# Breakout1v1.net
KiCad netlist of a schematic drawn in EAGLE
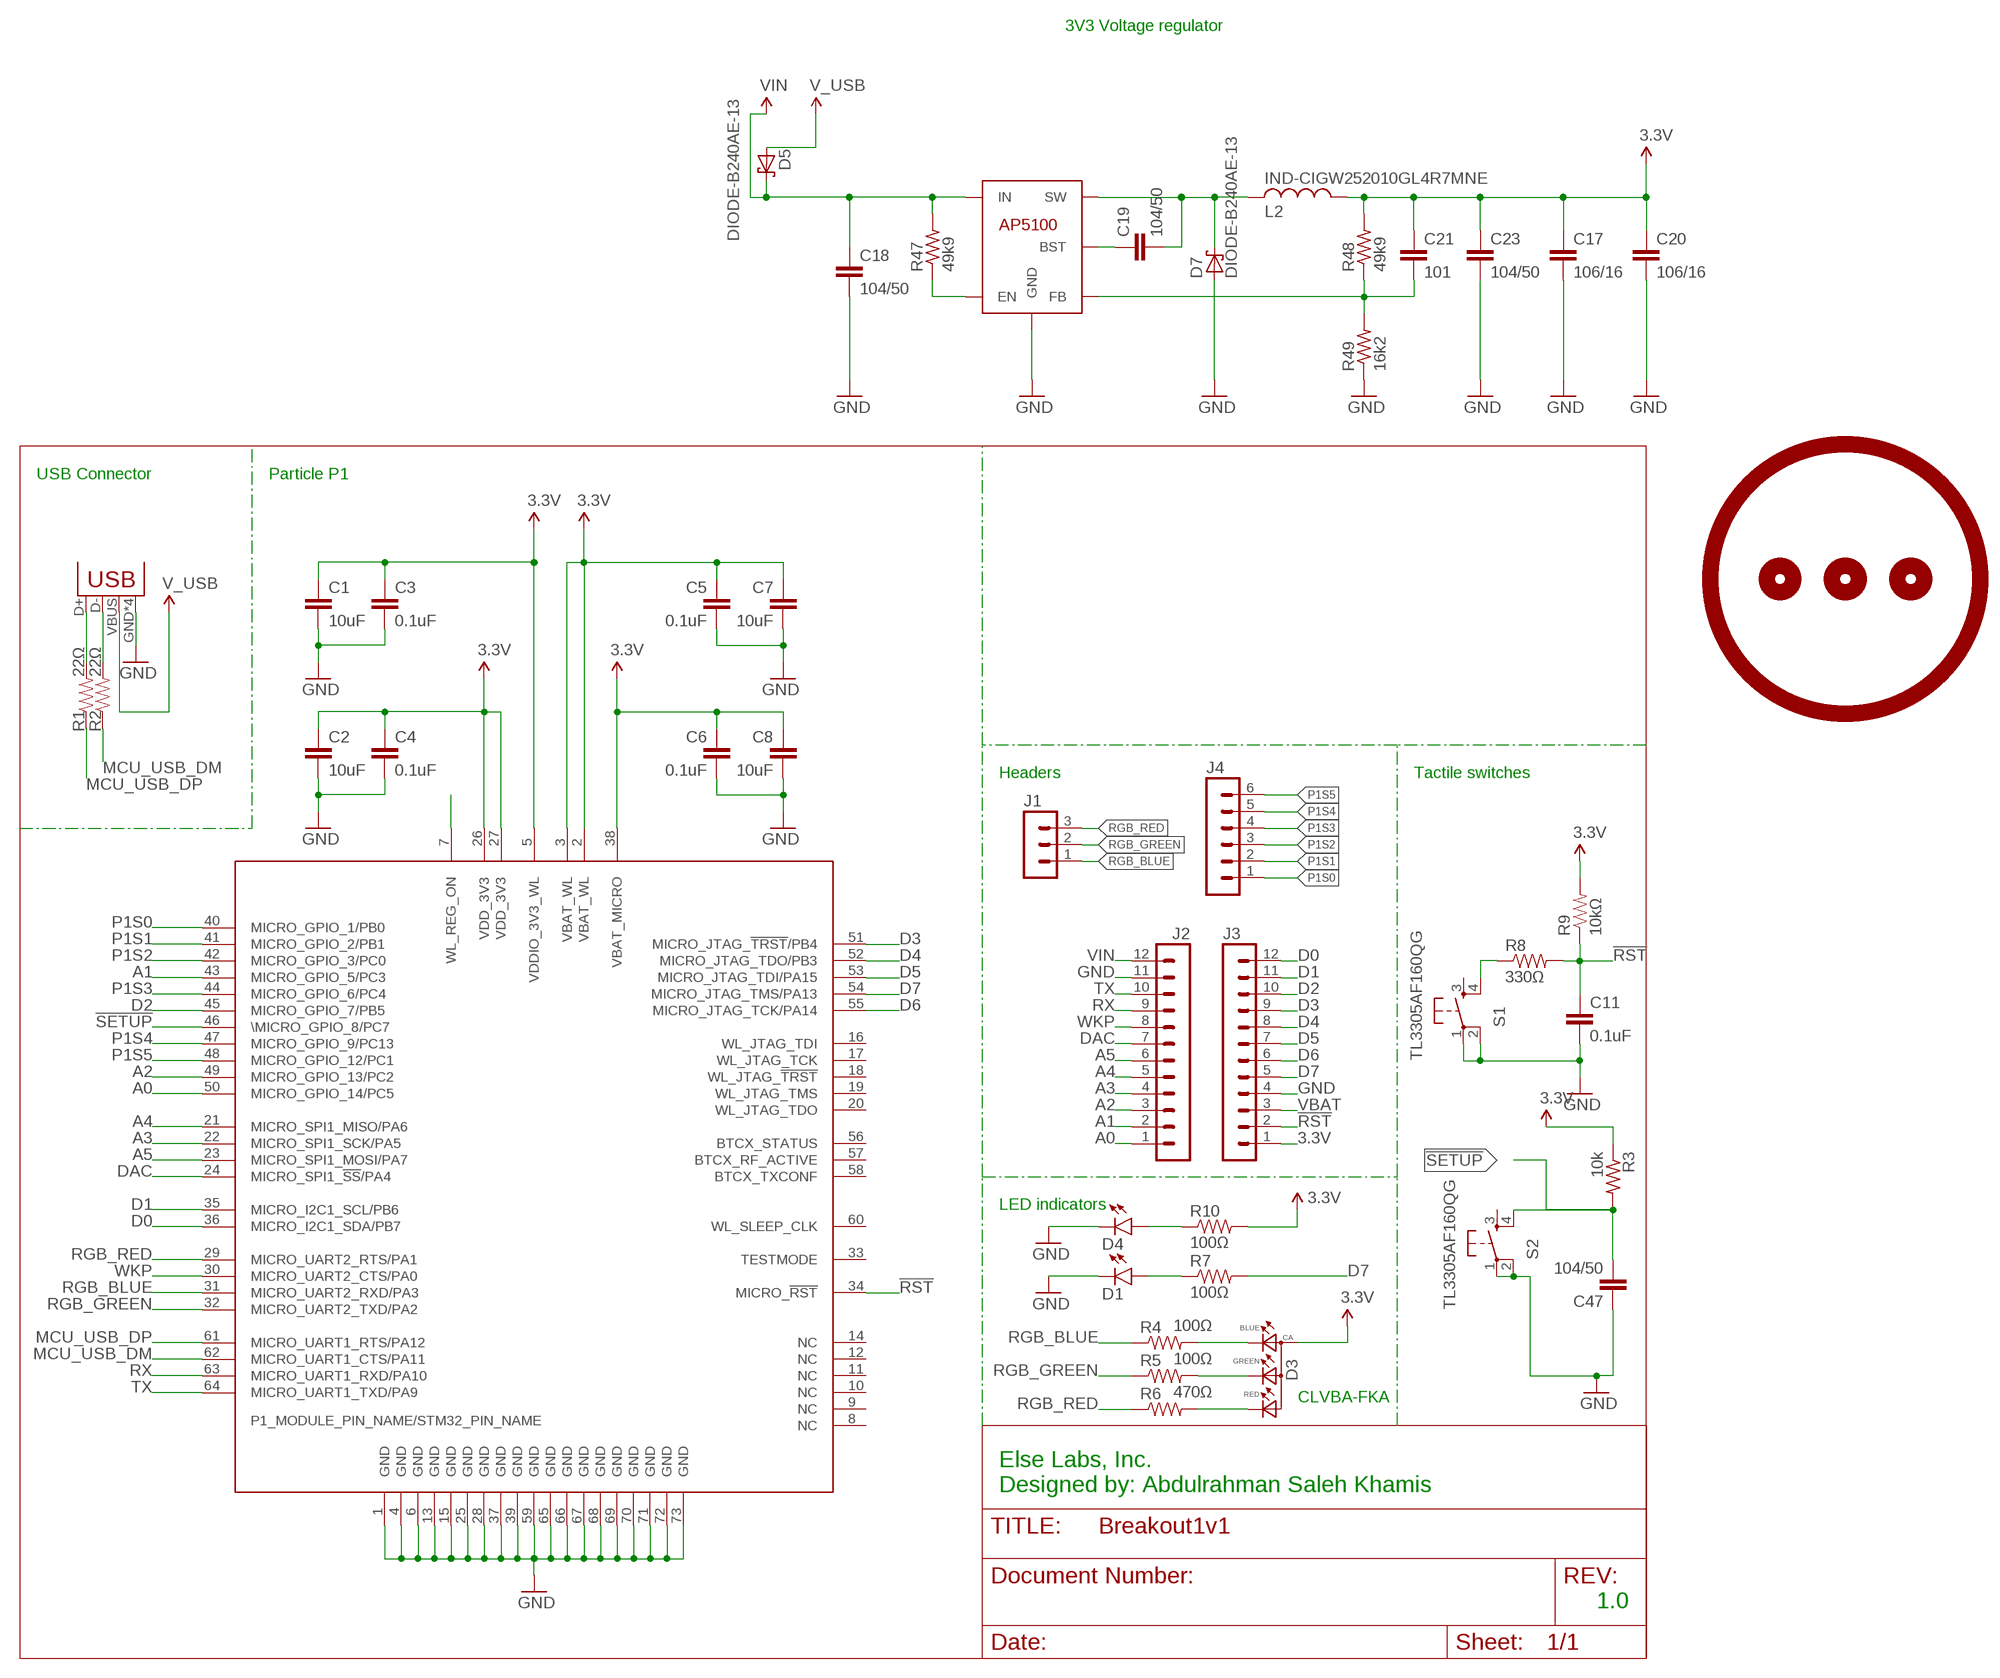
[diagram p0: schematic, sheet 1]

(export (version "E")
  (design (tool "Eeschema 10.0.6"))
  (components
    (comp (ref "C1")
      (value "10uF")
      (footprint "eagle-import:0805")
      (libsource (lib "eagle-import") (part "CAP0805"))
    )
    (comp (ref "C2")
      (value "10uF")
      (footprint "eagle-import:0805")
      (libsource (lib "eagle-import") (part "CAP0805"))
    )
    (comp (ref "C3")
      (value "0.1uF")
      (footprint "eagle-import:0805")
      (libsource (lib "eagle-import") (part "CAP0805"))
    )
    (comp (ref "C4")
      (value "0.1uF")
      (footprint "eagle-import:0805")
      (libsource (lib "eagle-import") (part "CAP0805"))
    )
    (comp (ref "C5")
      (value "0.1uF")
      (footprint "eagle-import:0805")
      (libsource (lib "eagle-import") (part "CAP0805"))
    )
    (comp (ref "C6")
      (value "0.1uF")
      (footprint "eagle-import:0805")
      (libsource (lib "eagle-import") (part "CAP0805"))
    )
    (comp (ref "C7")
      (value "10uF")
      (footprint "eagle-import:0805")
      (libsource (lib "eagle-import") (part "CAP0805"))
    )
    (comp (ref "C8")
      (value "10uF")
      (footprint "eagle-import:0805")
      (libsource (lib "eagle-import") (part "CAP0805"))
    )
    (comp (ref "C11")
      (value "0.1uF")
      (footprint "eagle-import:0805")
      (libsource (lib "eagle-import") (part "CAP0805"))
    )
    (comp (ref "C17")
      (value "106/16")
      (footprint "eagle-import:C0805")
      (libsource (lib "eagle-import") (part "C-EUC0805"))
    )
    (comp (ref "C18")
      (value "104/50")
      (footprint "eagle-import:C0603")
      (libsource (lib "eagle-import") (part "C-EUC0603"))
    )
    (comp (ref "C19")
      (value "104/50")
      (footprint "eagle-import:C0603")
      (libsource (lib "eagle-import") (part "C-EUC0603"))
    )
    (comp (ref "C20")
      (value "106/16")
      (footprint "eagle-import:C0805")
      (libsource (lib "eagle-import") (part "C-EUC0805"))
    )
    (comp (ref "C21")
      (value "101")
      (footprint "eagle-import:C0603")
      (libsource (lib "eagle-import") (part "C-EUC0603"))
    )
    (comp (ref "C23")
      (value "104/50")
      (footprint "eagle-import:C0603")
      (libsource (lib "eagle-import") (part "C-EUC0603"))
    )
    (comp (ref "C47")
      (value "104/50")
      (footprint "eagle-import:C0603")
      (libsource (lib "eagle-import") (part "C-EUC0603"))
    )
    (comp (ref "D1")
      (value "LED0603")
      (footprint "eagle-import:LED-0603")
      (libsource (lib "eagle-import") (part "LED0603"))
    )
    (comp (ref "D3")
      (value "CLVBA-FKAPLCC")
      (footprint "eagle-import:4-PLCC")
      (libsource (lib "eagle-import") (part "CLVBA-FKAPLCC"))
    )
    (comp (ref "D4")
      (value "LED0603")
      (footprint "eagle-import:LED-0603")
      (libsource (lib "eagle-import") (part "LED0603"))
    )
    (comp (ref "D5")
      (value "DIODE-B240AE-13")
      (footprint "eagle-import:DO-214AC")
      (libsource (lib "eagle-import") (part "DIODE-B240AE-13"))
    )
    (comp (ref "D7")
      (value "DIODE-B240AE-13")
      (footprint "eagle-import:DO-214AC")
      (libsource (lib "eagle-import") (part "DIODE-B240AE-13"))
    )
    (comp (ref "IC5")
      (value "SMSP-BUCK-AP5100")
      (footprint "eagle-import:SOT23-6")
      (libsource (lib "eagle-import") (part "SMSP-BUCK-AP5100"))
    )
    (comp (ref "J1")
      (value "MA03-1")
      (footprint "eagle-import:MA03-1")
      (libsource (lib "eagle-import") (part "MA03-1"))
    )
    (comp (ref "J2")
      (value "MA12-1")
      (footprint "eagle-import:MA12-1")
      (libsource (lib "eagle-import") (part "MA12-1"))
    )
    (comp (ref "J3")
      (value "MA12-1")
      (footprint "eagle-import:MA12-1")
      (libsource (lib "eagle-import") (part "MA12-1"))
    )
    (comp (ref "J4")
      (value "MA06-1")
      (footprint "eagle-import:MA06-1")
      (libsource (lib "eagle-import") (part "MA06-1"))
    )
    (comp (ref "JP1")
      (value "USBUSB-MICROB-SLOT-HOLE")
      (footprint "eagle-import:USB-MICROB-SLOT-HOLE")
      (libsource (lib "eagle-import") (part "USBUSB-MICROB-SLOT-HOLE"))
    )
    (comp (ref "L2")
      (value "IND-CIGW252010GL4R7MNE")
      (footprint "eagle-import:L2520")
      (libsource (lib "eagle-import") (part "IND-CIGW252010GL4R7MNE"))
    )
    (comp (ref "R1")
      (value "22Ω")
      (footprint "eagle-import:0805")
      (libsource (lib "eagle-import") (part "RESISTOR0805-RES"))
    )
    (comp (ref "R2")
      (value "22Ω")
      (footprint "eagle-import:0805")
      (libsource (lib "eagle-import") (part "RESISTOR0805-RES"))
    )
    (comp (ref "R3")
      (value "10k")
      (footprint "eagle-import:R0603")
      (libsource (lib "eagle-import") (part "R-US_R0603"))
    )
    (comp (ref "R4")
      (value "100Ω")
      (footprint "eagle-import:0805")
      (libsource (lib "eagle-import") (part "RESISTOR0805-RES"))
    )
    (comp (ref "R5")
      (value "100Ω")
      (footprint "eagle-import:0805")
      (libsource (lib "eagle-import") (part "RESISTOR0805-RES"))
    )
    (comp (ref "R6")
      (value "470Ω")
      (footprint "eagle-import:0805")
      (libsource (lib "eagle-import") (part "RESISTOR0805-RES"))
    )
    (comp (ref "R7")
      (value "100Ω")
      (footprint "eagle-import:0805")
      (libsource (lib "eagle-import") (part "RESISTOR0805-RES"))
    )
    (comp (ref "R8")
      (value "330Ω")
      (footprint "eagle-import:0805")
      (libsource (lib "eagle-import") (part "RESISTOR0805-RES"))
    )
    (comp (ref "R9")
      (value "10kΩ")
      (footprint "eagle-import:0805")
      (libsource (lib "eagle-import") (part "RESISTOR0805-RES"))
    )
    (comp (ref "R10")
      (value "100Ω")
      (footprint "eagle-import:0805")
      (libsource (lib "eagle-import") (part "RESISTOR0805-RES"))
    )
    (comp (ref "R47")
      (value "49k9")
      (footprint "eagle-import:R0603")
      (libsource (lib "eagle-import") (part "R-US_R0603"))
    )
    (comp (ref "R48")
      (value "49k9")
      (footprint "eagle-import:R0603")
      (libsource (lib "eagle-import") (part "R-US_R0603"))
    )
    (comp (ref "R49")
      (value "16k2")
      (footprint "eagle-import:R0603")
      (libsource (lib "eagle-import") (part "R-US_R0603"))
    )
    (comp (ref "S1")
      (value "TL3305AF160QG")
      (footprint "eagle-import:TACTILE_SWITCH_SMD_4.5X4.5MM")
      (libsource (lib "eagle-import") (part "SWITCH-MOMENTARY-4.5MX4.5M"))
    )
    (comp (ref "S2")
      (value "TL3305AF160QG")
      (footprint "eagle-import:TACTILE_SWITCH_SMD_4.5X4.5MM")
      (libsource (lib "eagle-import") (part "SWITCH-MOMENTARY-4.5MX4.5M"))
    )
    (comp (ref "U$1")
      (value "LOGO")
      (footprint "eagle-import:LOGO")
      (libsource (lib "eagle-import") (part "LOGO"))
    )
    (comp (ref "UC1")
      (value "P1")
      (footprint "eagle-import:WM-N-BM-14")
      (libsource (lib "eagle-import") (part "P1"))
    )
  )
  (nets
    (net (code "1") (name "/A0") (class "Default")
      (node (ref "J2") (pin "1") (pinfunction "1_1") (pintype "passive"))
      (node (ref "UC1") (pin "50") (pinfunction "MICRO_GPIO_14/PC5_50") (pintype "bidirectional"))
    )
    (net (code "2") (name "/A1") (class "Default")
      (node (ref "J2") (pin "2") (pinfunction "2_2") (pintype "passive"))
      (node (ref "UC1") (pin "43") (pinfunction "MICRO_GPIO_5/PC3_43") (pintype "bidirectional"))
    )
    (net (code "3") (name "/A2") (class "Default")
      (node (ref "J2") (pin "3") (pinfunction "3_3") (pintype "passive"))
      (node (ref "UC1") (pin "49") (pinfunction "MICRO_GPIO_13/PC2_49") (pintype "bidirectional"))
    )
    (net (code "4") (name "/A3") (class "Default")
      (node (ref "J2") (pin "4") (pinfunction "4_4") (pintype "passive"))
      (node (ref "UC1") (pin "22") (pinfunction "MICRO_SPI1_SCK/PA5_22") (pintype "bidirectional"))
    )
    (net (code "5") (name "/A4") (class "Default")
      (node (ref "J2") (pin "5") (pinfunction "5_5") (pintype "passive"))
      (node (ref "UC1") (pin "21") (pinfunction "MICRO_SPI1_MISO/PA6_21") (pintype "bidirectional"))
    )
    (net (code "6") (name "/A5") (class "Default")
      (node (ref "J2") (pin "6") (pinfunction "6_6") (pintype "passive"))
      (node (ref "UC1") (pin "23") (pinfunction "MICRO_SPI1_MOSI/PA7_23") (pintype "bidirectional"))
    )
    (net (code "7") (name "/D0") (class "Default")
      (node (ref "J3") (pin "12") (pinfunction "12_12") (pintype "passive"))
      (node (ref "UC1") (pin "36") (pinfunction "MICRO_I2C1_SDA/PB7_36") (pintype "bidirectional"))
    )
    (net (code "8") (name "/D1") (class "Default")
      (node (ref "J3") (pin "11") (pinfunction "11_11") (pintype "passive"))
      (node (ref "UC1") (pin "35") (pinfunction "MICRO_I2C1_SCL/PB6_35") (pintype "bidirectional"))
    )
    (net (code "9") (name "/D2") (class "Default")
      (node (ref "J3") (pin "10") (pinfunction "10_10") (pintype "passive"))
      (node (ref "UC1") (pin "45") (pinfunction "MICRO_GPIO_7/PB5_45") (pintype "bidirectional"))
    )
    (net (code "10") (name "/D3") (class "Default")
      (node (ref "J3") (pin "9") (pinfunction "9_9") (pintype "passive"))
      (node (ref "UC1") (pin "51") (pinfunction "MICRO_JTAG_~{TRST}/PB4_51") (pintype "bidirectional"))
    )
    (net (code "11") (name "/D4") (class "Default")
      (node (ref "J3") (pin "8") (pinfunction "8_8") (pintype "passive"))
      (node (ref "UC1") (pin "52") (pinfunction "MICRO_JTAG_TDO/PB3_52") (pintype "bidirectional"))
    )
    (net (code "12") (name "/D5") (class "Default")
      (node (ref "J3") (pin "7") (pinfunction "7_7") (pintype "passive"))
      (node (ref "UC1") (pin "53") (pinfunction "MICRO_JTAG_TDI/PA15_53") (pintype "bidirectional"))
    )
    (net (code "13") (name "/D6") (class "Default")
      (node (ref "J3") (pin "6") (pinfunction "6_6") (pintype "passive"))
      (node (ref "UC1") (pin "55") (pinfunction "MICRO_JTAG_TCK/PA14_55") (pintype "bidirectional"))
    )
    (net (code "14") (name "/D7") (class "Default")
      (node (ref "J3") (pin "5") (pinfunction "5_5") (pintype "passive"))
      (node (ref "R7") (pin "2") (pinfunction "2_2") (pintype "passive"))
      (node (ref "UC1") (pin "54") (pinfunction "MICRO_JTAG_TMS/PA13_54") (pintype "bidirectional"))
    )
    (net (code "15") (name "/DAC") (class "Default")
      (node (ref "J2") (pin "7") (pinfunction "7_7") (pintype "passive"))
      (node (ref "UC1") (pin "24") (pinfunction "MICRO_SPI1_~{SS}/PA4_24") (pintype "bidirectional"))
    )
    (net (code "16") (name "/MCU_USB_DM") (class "Default")
      (node (ref "R2") (pin "1") (pinfunction "1_1") (pintype "passive"))
      (node (ref "UC1") (pin "62") (pinfunction "MICRO_UART1_CTS/PA11_62") (pintype "bidirectional"))
    )
    (net (code "17") (name "/MCU_USB_DP") (class "Default")
      (node (ref "R1") (pin "1") (pinfunction "1_1") (pintype "passive"))
      (node (ref "UC1") (pin "61") (pinfunction "MICRO_UART1_RTS/PA12_61") (pintype "bidirectional"))
    )
    (net (code "18") (name "/RX") (class "Default")
      (node (ref "J2") (pin "9") (pinfunction "9_9") (pintype "passive"))
      (node (ref "UC1") (pin "63") (pinfunction "MICRO_UART1_RXD/PA10_63") (pintype "bidirectional"))
    )
    (net (code "19") (name "/TX") (class "Default")
      (node (ref "J2") (pin "10") (pinfunction "10_10") (pintype "passive"))
      (node (ref "UC1") (pin "64") (pinfunction "MICRO_UART1_TXD/PA9_64") (pintype "bidirectional"))
    )
    (net (code "20") (name "/VBAT") (class "Default")
      (node (ref "J3") (pin "3") (pinfunction "3_3") (pintype "passive"))
    )
    (net (code "21") (name "/WKP") (class "Default")
      (node (ref "J2") (pin "8") (pinfunction "8_8") (pintype "passive"))
      (node (ref "UC1") (pin "30") (pinfunction "MICRO_UART2_CTS/PA0_30") (pintype "bidirectional"))
    )
    (net (code "22") (name "/~{RST}") (class "Default")
      (node (ref "C11") (pin "1") (pinfunction "1_1") (pintype "passive"))
      (node (ref "J3") (pin "2") (pinfunction "2_2") (pintype "passive"))
      (node (ref "R8") (pin "2") (pinfunction "2_2") (pintype "passive"))
      (node (ref "R9") (pin "1") (pinfunction "1_1") (pintype "passive"))
      (node (ref "UC1") (pin "34") (pinfunction "MICRO_~{RST}_34") (pintype "bidirectional"))
    )
    (net (code "23") (name "/~{SETUP}") (class "Default")
      (node (ref "C47") (pin "2") (pinfunction "2_2") (pintype "passive"))
      (node (ref "R3") (pin "2") (pinfunction "2_2") (pintype "passive"))
      (node (ref "S2") (pin "4") (pinfunction "4_4") (pintype "passive"))
      (node (ref "UC1") (pin "46") (pinfunction "\\MICRO_GPIO_8/PC7_46") (pintype "bidirectional"))
    )
    (net (code "24") (name "3.3V") (class "Default")
      (node (ref "C1") (pin "1") (pinfunction "1_1") (pintype "passive"))
      (node (ref "C17") (pin "1") (pinfunction "1_1") (pintype "passive"))
      (node (ref "C2") (pin "1") (pinfunction "1_1") (pintype "passive"))
      (node (ref "C20") (pin "1") (pinfunction "1_1") (pintype "passive"))
      (node (ref "C21") (pin "1") (pinfunction "1_1") (pintype "passive"))
      (node (ref "C23") (pin "1") (pinfunction "1_1") (pintype "passive"))
      (node (ref "C3") (pin "1") (pinfunction "1_1") (pintype "passive"))
      (node (ref "C4") (pin "1") (pinfunction "1_1") (pintype "passive"))
      (node (ref "C5") (pin "1") (pinfunction "1_1") (pintype "passive"))
      (node (ref "C6") (pin "1") (pinfunction "1_1") (pintype "passive"))
      (node (ref "C7") (pin "1") (pinfunction "1_1") (pintype "passive"))
      (node (ref "C8") (pin "1") (pinfunction "1_1") (pintype "passive"))
      (node (ref "D3") (pin "2") (pinfunction "ANODE_2") (pintype "passive"))
      (node (ref "J3") (pin "1") (pinfunction "1_1") (pintype "passive"))
      (node (ref "L2") (pin "P$1") (pinfunction "1_P$1") (pintype "passive"))
      (node (ref "R10") (pin "2") (pinfunction "2_2") (pintype "passive"))
      (node (ref "R3") (pin "1") (pinfunction "1_1") (pintype "passive"))
      (node (ref "R48") (pin "2") (pinfunction "2_2") (pintype "passive"))
      (node (ref "R9") (pin "2") (pinfunction "2_2") (pintype "passive"))
      (node (ref "UC1") (pin "2") (pinfunction "VBAT_WL_2") (pintype "bidirectional"))
      (node (ref "UC1") (pin "26") (pinfunction "VDD_3V3_26") (pintype "bidirectional"))
      (node (ref "UC1") (pin "27") (pinfunction "VDD_3V3_27") (pintype "bidirectional"))
      (node (ref "UC1") (pin "3") (pinfunction "VBAT_WL_3") (pintype "bidirectional"))
      (node (ref "UC1") (pin "38") (pinfunction "VBAT_MICRO_38") (pintype "bidirectional"))
      (node (ref "UC1") (pin "5") (pinfunction "VDDIO_3V3_WL_5") (pintype "bidirectional"))
    )
    (net (code "25") (name "GND") (class "Default")
      (node (ref "C1") (pin "2") (pinfunction "2_2") (pintype "passive"))
      (node (ref "C11") (pin "2") (pinfunction "2_2") (pintype "passive"))
      (node (ref "C17") (pin "2") (pinfunction "2_2") (pintype "passive"))
      (node (ref "C18") (pin "2") (pinfunction "2_2") (pintype "passive"))
      (node (ref "C2") (pin "2") (pinfunction "2_2") (pintype "passive"))
      (node (ref "C20") (pin "2") (pinfunction "2_2") (pintype "passive"))
      (node (ref "C23") (pin "2") (pinfunction "2_2") (pintype "passive"))
      (node (ref "C3") (pin "2") (pinfunction "2_2") (pintype "passive"))
      (node (ref "C4") (pin "2") (pinfunction "2_2") (pintype "passive"))
      (node (ref "C47") (pin "1") (pinfunction "1_1") (pintype "passive"))
      (node (ref "C5") (pin "2") (pinfunction "2_2") (pintype "passive"))
      (node (ref "C6") (pin "2") (pinfunction "2_2") (pintype "passive"))
      (node (ref "C7") (pin "2") (pinfunction "2_2") (pintype "passive"))
      (node (ref "C8") (pin "2") (pinfunction "2_2") (pintype "passive"))
      (node (ref "D1") (pin "C") (pinfunction "C_C") (pintype "passive"))
      (node (ref "D4") (pin "C") (pinfunction "C_C") (pintype "passive"))
      (node (ref "D7") (pin "A") (pinfunction "A_A") (pintype "passive"))
      (node (ref "IC5") (pin "2") (pinfunction "GND_2") (pintype "bidirectional"))
      (node (ref "J2") (pin "11") (pinfunction "11_11") (pintype "passive"))
      (node (ref "J3") (pin "4") (pinfunction "4_4") (pintype "passive"))
      (node (ref "JP1") (pin "GND") (pinfunction "GND_GND") (pintype "bidirectional"))
      (node (ref "JP1") (pin "P$1") (pinfunction "GND_P$1") (pintype "bidirectional"))
      (node (ref "JP1") (pin "P$2") (pinfunction "GND_P$2") (pintype "bidirectional"))
      (node (ref "JP1") (pin "P$3") (pinfunction "GND_P$3") (pintype "bidirectional"))
      (node (ref "R49") (pin "1") (pinfunction "1_1") (pintype "passive"))
      (node (ref "S1") (pin "1") (pinfunction "1_1") (pintype "passive"))
      (node (ref "S1") (pin "2") (pinfunction "2_2") (pintype "passive"))
      (node (ref "S2") (pin "1") (pinfunction "1_1") (pintype "passive"))
      (node (ref "S2") (pin "2") (pinfunction "2_2") (pintype "passive"))
      (node (ref "UC1") (pin "1") (pinfunction "GND_1") (pintype "bidirectional"))
      (node (ref "UC1") (pin "13") (pinfunction "GND_13") (pintype "bidirectional"))
      (node (ref "UC1") (pin "15") (pinfunction "GND_15") (pintype "bidirectional"))
      (node (ref "UC1") (pin "25") (pinfunction "GND_25") (pintype "bidirectional"))
      (node (ref "UC1") (pin "28") (pinfunction "GND_28") (pintype "bidirectional"))
      (node (ref "UC1") (pin "37") (pinfunction "GND_37") (pintype "bidirectional"))
      (node (ref "UC1") (pin "39") (pinfunction "GND_39") (pintype "bidirectional"))
      (node (ref "UC1") (pin "4") (pinfunction "GND_4") (pintype "bidirectional"))
      (node (ref "UC1") (pin "59") (pinfunction "GND_59") (pintype "bidirectional"))
      (node (ref "UC1") (pin "6") (pinfunction "GND_6") (pintype "bidirectional"))
      (node (ref "UC1") (pin "65") (pinfunction "GND_65") (pintype "bidirectional"))
      (node (ref "UC1") (pin "66") (pinfunction "GND_66") (pintype "bidirectional"))
      (node (ref "UC1") (pin "67") (pinfunction "GND_67") (pintype "bidirectional"))
      (node (ref "UC1") (pin "68") (pinfunction "GND_68") (pintype "bidirectional"))
      (node (ref "UC1") (pin "69") (pinfunction "GND_69") (pintype "bidirectional"))
      (node (ref "UC1") (pin "70") (pinfunction "GND_70") (pintype "bidirectional"))
      (node (ref "UC1") (pin "71") (pinfunction "GND_71") (pintype "bidirectional"))
      (node (ref "UC1") (pin "72") (pinfunction "GND_72") (pintype "bidirectional"))
      (node (ref "UC1") (pin "73") (pinfunction "GND_73") (pintype "bidirectional"))
    )
    (net (code "26") (name "Net-(D1-PadA)") (class "Default")
      (node (ref "D1") (pin "A") (pinfunction "A_A") (pintype "passive"))
      (node (ref "R7") (pin "1") (pinfunction "1_1") (pintype "passive"))
    )
    (net (code "27") (name "Net-(D3-BLUE)") (class "Default")
      (node (ref "D3") (pin "3") (pinfunction "BLUE_3") (pintype "passive"))
      (node (ref "R4") (pin "2") (pinfunction "2_2") (pintype "passive"))
    )
    (net (code "28") (name "Net-(D3-GREEN)") (class "Default")
      (node (ref "D3") (pin "4") (pinfunction "GREEN_4") (pintype "passive"))
      (node (ref "R5") (pin "2") (pinfunction "2_2") (pintype "passive"))
    )
    (net (code "29") (name "Net-(D3-RED)") (class "Default")
      (node (ref "D3") (pin "1") (pinfunction "RED_1") (pintype "passive"))
      (node (ref "R6") (pin "2") (pinfunction "2_2") (pintype "passive"))
    )
    (net (code "30") (name "Net-(D4-PadA)") (class "Default")
      (node (ref "D4") (pin "A") (pinfunction "A_A") (pintype "passive"))
      (node (ref "R10") (pin "1") (pinfunction "1_1") (pintype "passive"))
    )
    (net (code "31") (name "Net-(IC5-BST)") (class "Default")
      (node (ref "C19") (pin "1") (pinfunction "1_1") (pintype "passive"))
      (node (ref "IC5") (pin "1") (pinfunction "BST_1") (pintype "bidirectional"))
    )
    (net (code "32") (name "Net-(IC5-EN)") (class "Default")
      (node (ref "IC5") (pin "4") (pinfunction "EN_4") (pintype "bidirectional"))
      (node (ref "R47") (pin "1") (pinfunction "1_1") (pintype "passive"))
    )
    (net (code "33") (name "Net-(IC5-FB)") (class "Default")
      (node (ref "C21") (pin "2") (pinfunction "2_2") (pintype "passive"))
      (node (ref "IC5") (pin "3") (pinfunction "FB_3") (pintype "bidirectional"))
      (node (ref "R48") (pin "1") (pinfunction "1_1") (pintype "passive"))
      (node (ref "R49") (pin "2") (pinfunction "2_2") (pintype "passive"))
    )
    (net (code "34") (name "Net-(IC5-SW)") (class "Default")
      (node (ref "C19") (pin "2") (pinfunction "2_2") (pintype "passive"))
      (node (ref "D7") (pin "C") (pinfunction "C_C") (pintype "passive"))
      (node (ref "IC5") (pin "6") (pinfunction "SW_6") (pintype "bidirectional"))
      (node (ref "L2") (pin "P$2") (pinfunction "2_P$2") (pintype "passive"))
    )
    (net (code "35") (name "Net-(JP1-PadD+)") (class "Default")
      (node (ref "JP1") (pin "D+") (pinfunction "D+_D+") (pintype "bidirectional"))
      (node (ref "R1") (pin "2") (pinfunction "2_2") (pintype "passive"))
    )
    (net (code "36") (name "Net-(JP1-PadD-)") (class "Default")
      (node (ref "JP1") (pin "D-") (pinfunction "D-_D-") (pintype "bidirectional"))
      (node (ref "R2") (pin "2") (pinfunction "2_2") (pintype "passive"))
    )
    (net (code "37") (name "Net-(R8-Pad1)") (class "Default")
      (node (ref "R8") (pin "1") (pinfunction "1_1") (pintype "passive"))
      (node (ref "S1") (pin "4") (pinfunction "4_4") (pintype "passive"))
    )
    (net (code "38") (name "P1S0") (class "Default")
      (node (ref "J4") (pin "1") (pinfunction "1_1") (pintype "passive"))
      (node (ref "UC1") (pin "40") (pinfunction "MICRO_GPIO_1/PB0_40") (pintype "bidirectional"))
    )
    (net (code "39") (name "P1S1") (class "Default")
      (node (ref "J4") (pin "2") (pinfunction "2_2") (pintype "passive"))
      (node (ref "UC1") (pin "41") (pinfunction "MICRO_GPIO_2/PB1_41") (pintype "bidirectional"))
    )
    (net (code "40") (name "P1S2") (class "Default")
      (node (ref "J4") (pin "3") (pinfunction "3_3") (pintype "passive"))
      (node (ref "UC1") (pin "42") (pinfunction "MICRO_GPIO_3/PC0_42") (pintype "bidirectional"))
    )
    (net (code "41") (name "P1S3") (class "Default")
      (node (ref "J4") (pin "4") (pinfunction "4_4") (pintype "passive"))
      (node (ref "UC1") (pin "44") (pinfunction "MICRO_GPIO_6/PC4_44") (pintype "bidirectional"))
    )
    (net (code "42") (name "P1S4") (class "Default")
      (node (ref "J4") (pin "5") (pinfunction "5_5") (pintype "passive"))
      (node (ref "UC1") (pin "47") (pinfunction "MICRO_GPIO_9/PC13_47") (pintype "bidirectional"))
    )
    (net (code "43") (name "P1S5") (class "Default")
      (node (ref "J4") (pin "6") (pinfunction "6_6") (pintype "passive"))
      (node (ref "UC1") (pin "48") (pinfunction "MICRO_GPIO_12/PC1_48") (pintype "bidirectional"))
    )
    (net (code "44") (name "RGB_BLUE") (class "Default")
      (node (ref "J1") (pin "1") (pinfunction "1_1") (pintype "passive"))
      (node (ref "R4") (pin "1") (pinfunction "1_1") (pintype "passive"))
      (node (ref "UC1") (pin "31") (pinfunction "MICRO_UART2_RXD/PA3_31") (pintype "bidirectional"))
    )
    (net (code "45") (name "RGB_GREEN") (class "Default")
      (node (ref "J1") (pin "2") (pinfunction "2_2") (pintype "passive"))
      (node (ref "R5") (pin "1") (pinfunction "1_1") (pintype "passive"))
      (node (ref "UC1") (pin "32") (pinfunction "MICRO_UART2_TXD/PA2_32") (pintype "bidirectional"))
    )
    (net (code "46") (name "RGB_RED") (class "Default")
      (node (ref "J1") (pin "3") (pinfunction "3_3") (pintype "passive"))
      (node (ref "R6") (pin "1") (pinfunction "1_1") (pintype "passive"))
      (node (ref "UC1") (pin "29") (pinfunction "MICRO_UART2_RTS/PA1_29") (pintype "bidirectional"))
    )
    (net (code "47") (name "VIN") (class "Default")
      (node (ref "C18") (pin "1") (pinfunction "1_1") (pintype "passive"))
      (node (ref "D5") (pin "C") (pinfunction "C_C") (pintype "passive"))
      (node (ref "IC5") (pin "5") (pinfunction "IN_5") (pintype "bidirectional"))
      (node (ref "J2") (pin "12") (pinfunction "12_12") (pintype "passive"))
      (node (ref "R47") (pin "2") (pinfunction "2_2") (pintype "passive"))
    )
    (net (code "48") (name "V_USB") (class "Default")
      (node (ref "D5") (pin "A") (pinfunction "A_A") (pintype "passive"))
      (node (ref "JP1") (pin "VBUS") (pinfunction "VBUS_VBUS") (pintype "bidirectional"))
    )
    (net (code "49") (name "unconnected-(S1-Pad3)") (class "Default")
      (node (ref "S1") (pin "3") (pinfunction "3_3") (pintype "passive"))
    )
    (net (code "50") (name "unconnected-(S2-Pad3)") (class "Default")
      (node (ref "S2") (pin "3") (pinfunction "3_3") (pintype "passive"))
    )
    (net (code "51") (name "unconnected-(UC1-BTCX_RF_ACTIVE-Pad57)") (class "Default")
      (node (ref "UC1") (pin "57") (pinfunction "BTCX_RF_ACTIVE_57") (pintype "bidirectional"))
    )
    (net (code "52") (name "unconnected-(UC1-BTCX_STATUS-Pad56)") (class "Default")
      (node (ref "UC1") (pin "56") (pinfunction "BTCX_STATUS_56") (pintype "bidirectional"))
    )
    (net (code "53") (name "unconnected-(UC1-BTCX_TXCONF-Pad58)") (class "Default")
      (node (ref "UC1") (pin "58") (pinfunction "BTCX_TXCONF_58") (pintype "bidirectional"))
    )
    (net (code "54") (name "unconnected-(UC1-NC-Pad8)") (class "Default")
      (node (ref "UC1") (pin "8") (pinfunction "NC_8") (pintype "bidirectional"))
    )
    (net (code "55") (name "unconnected-(UC1-NC-Pad9)") (class "Default")
      (node (ref "UC1") (pin "9") (pinfunction "NC_9") (pintype "bidirectional"))
    )
    (net (code "56") (name "unconnected-(UC1-NC-Pad10)") (class "Default")
      (node (ref "UC1") (pin "10") (pinfunction "NC_10") (pintype "bidirectional"))
    )
    (net (code "57") (name "unconnected-(UC1-NC-Pad11)") (class "Default")
      (node (ref "UC1") (pin "11") (pinfunction "NC_11") (pintype "bidirectional"))
    )
    (net (code "58") (name "unconnected-(UC1-NC-Pad12)") (class "Default")
      (node (ref "UC1") (pin "12") (pinfunction "NC_12") (pintype "bidirectional"))
    )
    (net (code "59") (name "unconnected-(UC1-NC-Pad14)") (class "Default")
      (node (ref "UC1") (pin "14") (pinfunction "NC_14") (pintype "bidirectional"))
    )
    (net (code "60") (name "unconnected-(UC1-TESTMODE-Pad33)") (class "Default")
      (node (ref "UC1") (pin "33") (pinfunction "TESTMODE_33") (pintype "bidirectional"))
    )
    (net (code "61") (name "unconnected-(UC1-WL_JTAG_TCK-Pad17)") (class "Default")
      (node (ref "UC1") (pin "17") (pinfunction "WL_JTAG_TCK_17") (pintype "bidirectional"))
    )
    (net (code "62") (name "unconnected-(UC1-WL_JTAG_TDI-Pad16)") (class "Default")
      (node (ref "UC1") (pin "16") (pinfunction "WL_JTAG_TDI_16") (pintype "bidirectional"))
    )
    (net (code "63") (name "unconnected-(UC1-WL_JTAG_TDO-Pad20)") (class "Default")
      (node (ref "UC1") (pin "20") (pinfunction "WL_JTAG_TDO_20") (pintype "bidirectional"))
    )
    (net (code "64") (name "unconnected-(UC1-WL_JTAG_TMS-Pad19)") (class "Default")
      (node (ref "UC1") (pin "19") (pinfunction "WL_JTAG_TMS_19") (pintype "bidirectional"))
    )
    (net (code "65") (name "unconnected-(UC1-WL_JTAG_~{TRST}-Pad18)") (class "Default")
      (node (ref "UC1") (pin "18") (pinfunction "WL_JTAG_~{TRST}_18") (pintype "bidirectional"))
    )
    (net (code "66") (name "unconnected-(UC1-WL_REG_ON-Pad7)") (class "Default")
      (node (ref "UC1") (pin "7") (pinfunction "WL_REG_ON_7") (pintype "bidirectional"))
    )
    (net (code "67") (name "unconnected-(UC1-WL_SLEEP_CLK-Pad60)") (class "Default")
      (node (ref "UC1") (pin "60") (pinfunction "WL_SLEEP_CLK_60") (pintype "bidirectional"))
    )
  )
)
